# board_1_4_FixMosfetGND_v.net
KiCad netlist of a schematic drawn in EAGLE
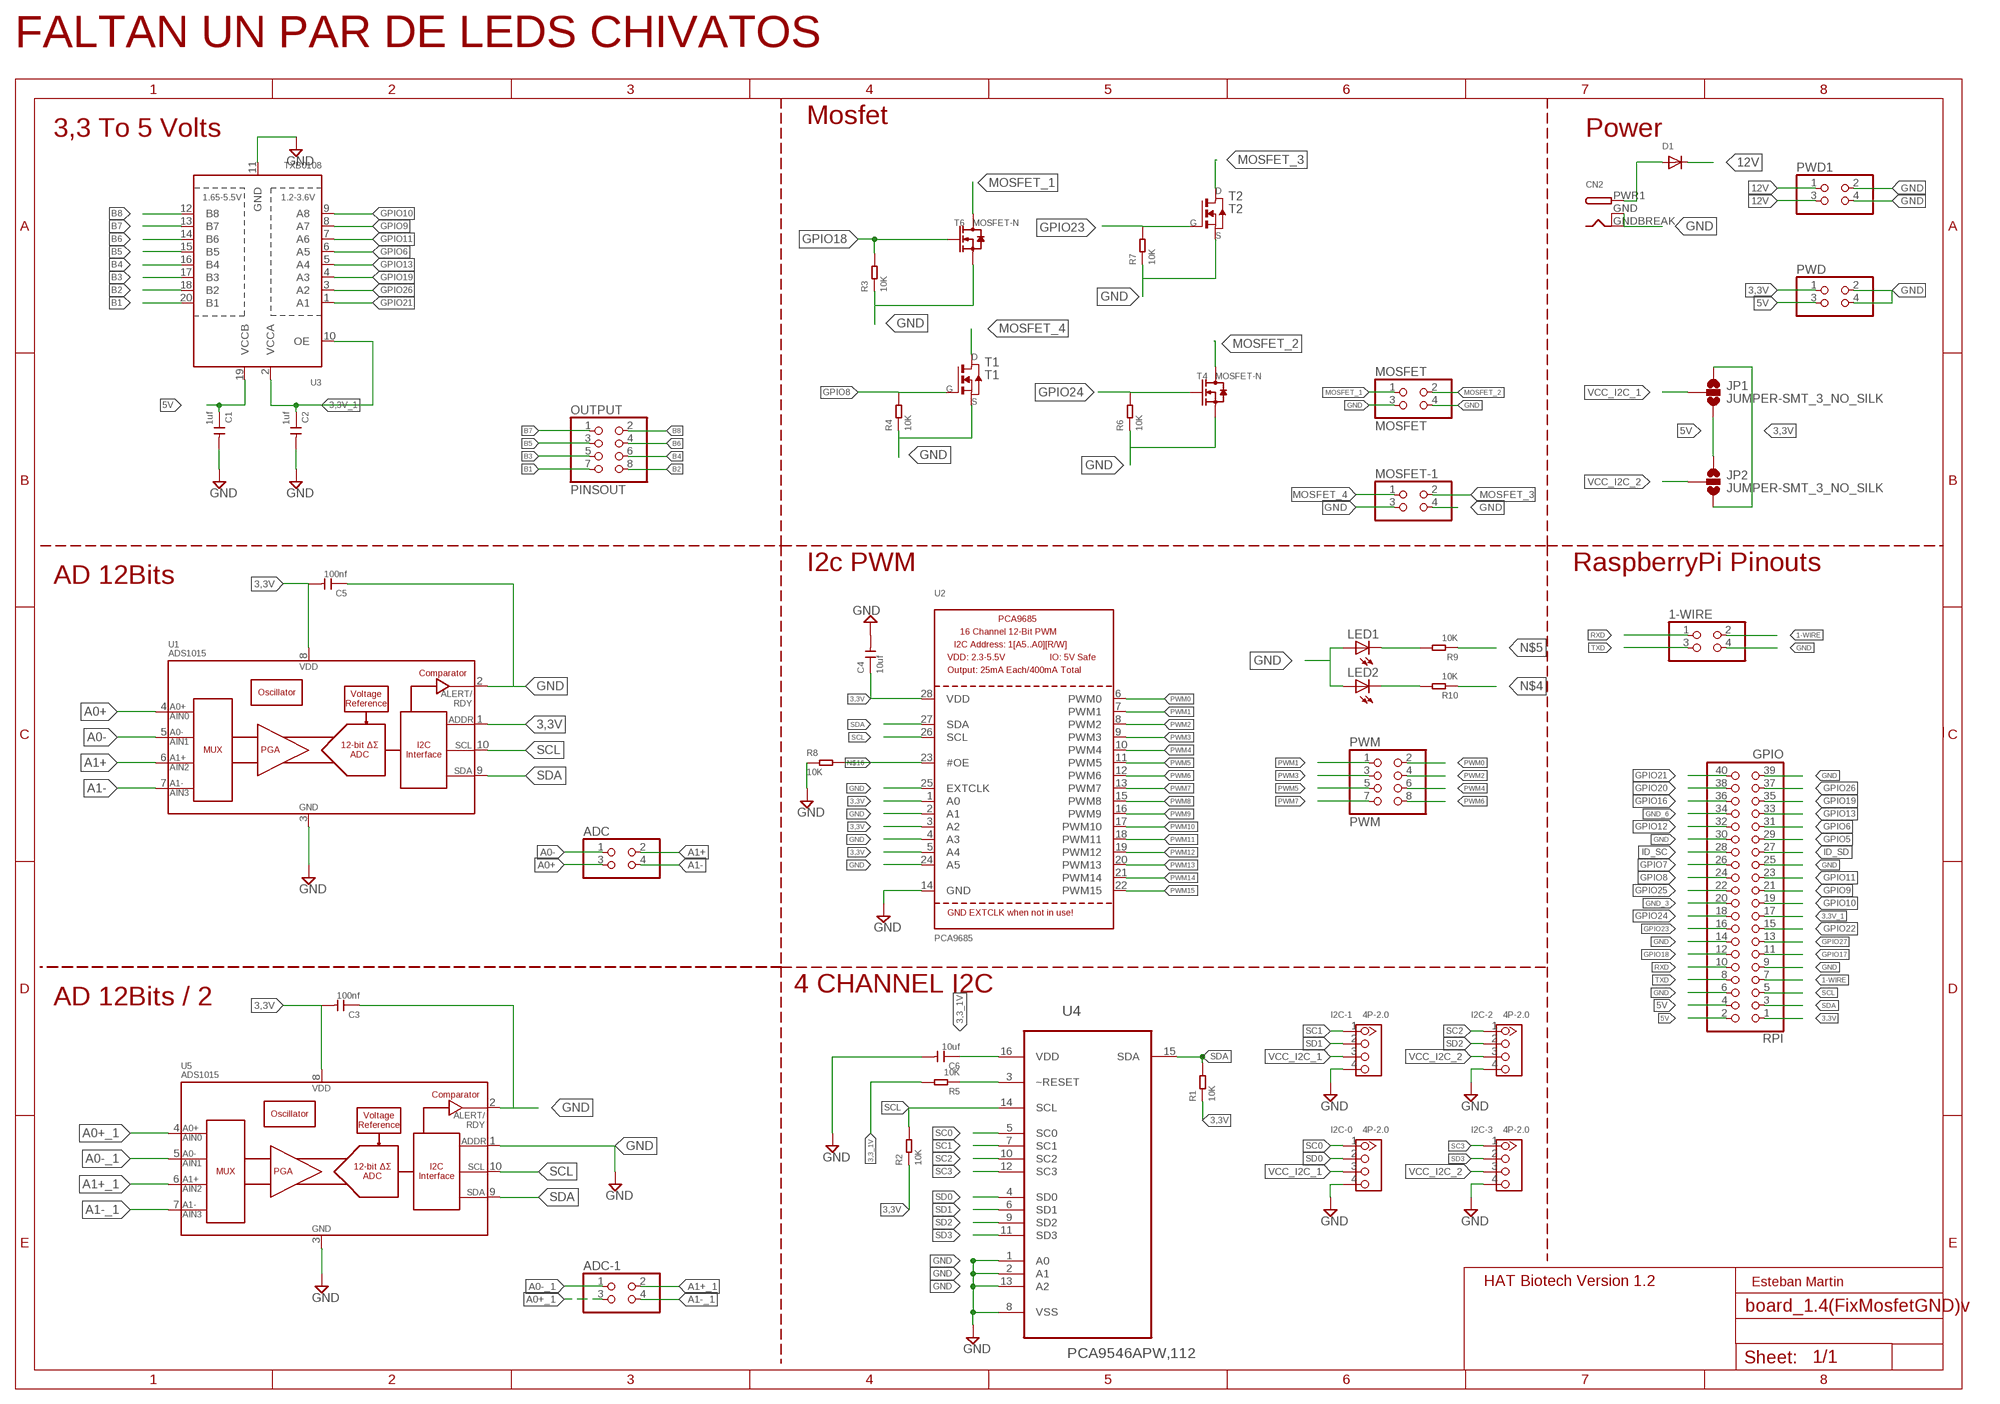
[diagram p0: schematic, sheet 1]

(export (version "E")
  (design (tool "Eeschema 10.0.6"))
  (components
    (comp (ref "1-WIRE")
      (value "PINHD-2X2")
      (footprint "eagle-import:2X02")
      (libsource (lib "eagle-import") (part "PINHD-2X2"))
    )
    (comp (ref "ADC")
      (value "PINHD-2X2")
      (footprint "eagle-import:2X02")
      (libsource (lib "eagle-import") (part "PINHD-2X2"))
    )
    (comp (ref "ADC-1")
      (value "PINHD-2X2")
      (footprint "eagle-import:2X02")
      (libsource (lib "eagle-import") (part "PINHD-2X2"))
    )
    (comp (ref "C1")
      (value "1uf")
      (footprint "eagle-import:C0805")
      (fields (field (name "MPN") "CC0805KKX7R8BB105"))
      (libsource (lib "eagle-import") (part "CERAMIC-1UF-25V-10%-X7R(0805)"))
    )
    (comp (ref "C2")
      (value "1uf")
      (footprint "eagle-import:C0805")
      (fields (field (name "MPN") "CC0805KKX7R8BB105"))
      (libsource (lib "eagle-import") (part "CERAMIC-1UF-25V-10%-X7R(0805)"))
    )
    (comp (ref "C3")
      (value "100nf")
      (footprint "eagle-import:C0805")
      (fields (field (name "MPN") "CC0805KRX7R9BB104"))
      (libsource (lib "eagle-import") (part "CERAMIC-100NF-50V-10%-X7R(0805)"))
    )
    (comp (ref "C4")
      (value "10uf")
      (footprint "eagle-import:C0805")
      (fields (field (name "MPN") "CC0805KKX7R8BB105"))
      (libsource (lib "eagle-import") (part "CERAMIC-1UF-25V-10%-X7R(0805)"))
    )
    (comp (ref "C5")
      (value "100nf")
      (footprint "eagle-import:C0805")
      (fields (field (name "MPN") "CC0805KRX7R9BB104"))
      (libsource (lib "eagle-import") (part "CERAMIC-100NF-50V-10%-X7R(0805)"))
    )
    (comp (ref "C6")
      (value "10uf")
      (footprint "eagle-import:C0805")
      (fields (field (name "MPN") "CC0805KKX7R8BB105"))
      (libsource (lib "eagle-import") (part "CERAMIC-1UF-25V-10%-X7R(0805)"))
    )
    (comp (ref "CN2")
      (value "DCBARRELSMT")
      (footprint "eagle-import:DCJACK_2MM_SMT")
      (libsource (lib "eagle-import") (part "DCBARRELSMT"))
    )
    (comp (ref "D1")
      (value "DIODESOD-123")
      (footprint "eagle-import:SOD-123")
      (libsource (lib "eagle-import") (part "DIODESOD-123"))
    )
    (comp (ref "I2C-0")
      (value "4P-2.0")
      (footprint "eagle-import:HW4-2.0")
      (libsource (lib "eagle-import") (part "GROVE-CONNECTOR-DIP(4P-2.0)"))
    )
    (comp (ref "I2C-1")
      (value "4P-2.0")
      (footprint "eagle-import:HW4-2.0")
      (libsource (lib "eagle-import") (part "GROVE-CONNECTOR-DIP(4P-2.0)"))
    )
    (comp (ref "I2C-2")
      (value "4P-2.0")
      (footprint "eagle-import:HW4-2.0")
      (libsource (lib "eagle-import") (part "GROVE-CONNECTOR-DIP(4P-2.0)"))
    )
    (comp (ref "I2C-3")
      (value "4P-2.0")
      (footprint "eagle-import:HW4-2.0")
      (libsource (lib "eagle-import") (part "GROVE-CONNECTOR-DIP(4P-2.0)"))
    )
    (comp (ref "JP1")
      (value "JUMPER-SMT_3_NO_SILK")
      (footprint "eagle-import:SMT-JUMPER_3_NO_SILK")
      (libsource (lib "eagle-import") (part "JUMPER-SMT_3_NO_SILK"))
    )
    (comp (ref "JP2")
      (value "JUMPER-SMT_3_NO_SILK")
      (footprint "eagle-import:SMT-JUMPER_3_NO_SILK")
      (libsource (lib "eagle-import") (part "JUMPER-SMT_3_NO_SILK"))
    )
    (comp (ref "LED1")
      (value "LED")
      (footprint "eagle-import:SMARTLED-TTW")
      (libsource (lib "eagle-import") (part "LED"))
    )
    (comp (ref "LED2")
      (value "LED")
      (footprint "eagle-import:SMARTLED-TTW")
      (libsource (lib "eagle-import") (part "LED"))
    )
    (comp (ref "MOSFET")
      (value "MOSFET")
      (footprint "eagle-import:2X02")
      (libsource (lib "eagle-import") (part "PINHD-2X2"))
    )
    (comp (ref "MOSFET-1")
      (value "PINHD-2X2")
      (footprint "eagle-import:2X02")
      (libsource (lib "eagle-import") (part "PINHD-2X2"))
    )
    (comp (ref "OUTPUT")
      (value "PINSOUT")
      (footprint "eagle-import:2X04")
      (libsource (lib "eagle-import") (part "PINHD-2X4"))
    )
    (comp (ref "PWD")
      (value "PINHD-2X2")
      (footprint "eagle-import:2X02")
      (libsource (lib "eagle-import") (part "PINHD-2X2"))
    )
    (comp (ref "PWD1")
      (value "PINHD-2X2")
      (footprint "eagle-import:2X02")
      (libsource (lib "eagle-import") (part "PINHD-2X2"))
    )
    (comp (ref "PWM")
      (value "PWM")
      (footprint "eagle-import:2X04")
      (libsource (lib "eagle-import") (part "PINHD-2X4"))
    )
    (comp (ref "R1")
      (value "10K")
      (footprint "eagle-import:R0805")
      (fields (field (name "MPN") "RC0805FR-0710KL"))
      (libsource (lib "eagle-import") (part "SMD-RES-10K-1%-1/8W(0805)"))
    )
    (comp (ref "R2")
      (value "10K")
      (footprint "eagle-import:R0805")
      (fields (field (name "MPN") "RC0805FR-0710KL"))
      (libsource (lib "eagle-import") (part "SMD-RES-10K-1%-1/8W(0805)"))
    )
    (comp (ref "R3")
      (value "10K")
      (footprint "eagle-import:R0805")
      (fields (field (name "MPN") "RC0805FR-0710KL"))
      (libsource (lib "eagle-import") (part "SMD-RES-10K-1%-1/8W(0805)"))
    )
    (comp (ref "R4")
      (value "10K")
      (footprint "eagle-import:R0805")
      (fields (field (name "MPN") "RC0805FR-0710KL"))
      (libsource (lib "eagle-import") (part "SMD-RES-10K-1%-1/8W(0805)"))
    )
    (comp (ref "R5")
      (value "10K")
      (footprint "eagle-import:R0805")
      (fields (field (name "MPN") "RC0805FR-0710KL"))
      (libsource (lib "eagle-import") (part "SMD-RES-10K-1%-1/8W(0805)"))
    )
    (comp (ref "R6")
      (value "10K")
      (footprint "eagle-import:R0805")
      (fields (field (name "MPN") "RC0805FR-0710KL"))
      (libsource (lib "eagle-import") (part "SMD-RES-10K-1%-1/8W(0805)"))
    )
    (comp (ref "R7")
      (value "10K")
      (footprint "eagle-import:R0805")
      (fields (field (name "MPN") "RC0805FR-0710KL"))
      (libsource (lib "eagle-import") (part "SMD-RES-10K-1%-1/8W(0805)"))
    )
    (comp (ref "R8")
      (value "10K")
      (footprint "eagle-import:R0805")
      (fields (field (name "MPN") "RC0805FR-0710KL"))
      (libsource (lib "eagle-import") (part "SMD-RES-10K-1%-1/8W(0805)"))
    )
    (comp (ref "R9")
      (value "10K")
      (footprint "eagle-import:R0805")
      (fields (field (name "MPN") "RC0805FR-0710KL"))
      (libsource (lib "eagle-import") (part "SMD-RES-10K-1%-1/8W(0805)"))
    )
    (comp (ref "R10")
      (value "10K")
      (footprint "eagle-import:R0805")
      (fields (field (name "MPN") "RC0805FR-0710KL"))
      (libsource (lib "eagle-import") (part "SMD-RES-10K-1%-1/8W(0805)"))
    )
    (comp (ref "RPI")
      (value "GPIO")
      (footprint "eagle-import:2X20")
      (libsource (lib "eagle-import") (part "PINHD-2X20"))
    )
    (comp (ref "T1")
      (value "T1")
      (footprint "eagle-import:TO252")
      (libsource (lib "eagle-import") (part "NMOSFETTO252"))
    )
    (comp (ref "T2")
      (value "T2")
      (footprint "eagle-import:TO252")
      (libsource (lib "eagle-import") (part "NMOSFETTO252"))
    )
    (comp (ref "T4")
      (value "MOSFET-N")
      (footprint "eagle-import:SOT-23")
      (libsource (lib "eagle-import") (part "MOSFET-N"))
    )
    (comp (ref "T6")
      (value "MOSFET-N")
      (footprint "eagle-import:SOT-23")
      (libsource (lib "eagle-import") (part "MOSFET-N"))
    )
    (comp (ref "U1")
      (value "ADS1015")
      (footprint "eagle-import:MSOP10")
      (libsource (lib "eagle-import") (part "ADS1015"))
    )
    (comp (ref "U2")
      (value "PCA9685")
      (footprint "eagle-import:TSSOP28")
      (libsource (lib "eagle-import") (part "PCA9685"))
    )
    (comp (ref "U3")
      (value "TXB0108")
      (footprint "eagle-import:TSSOP20")
      (libsource (lib "eagle-import") (part "TXB0108PWR"))
    )
    (comp (ref "U4")
      (value "PCA9546APW,112")
      (footprint "eagle-import:SOP65P640X110-16N")
      (libsource (lib "eagle-import") (part "PCA9546APW,112"))
    )
    (comp (ref "U5")
      (value "ADS1015")
      (footprint "eagle-import:MSOP10")
      (libsource (lib "eagle-import") (part "ADS1015"))
    )
  )
  (nets
    (net (code "1") (name "1-WIRE") (class "Default")
      (node (ref "1-WIRE") (pin "2") (pinfunction "2_2") (pintype "passive"))
      (node (ref "RPI") (pin "7") (pinfunction "7_7") (pintype "passive"))
    )
    (net (code "2") (name "3,3V") (class "Default")
      (node (ref "C3") (pin "2") (pinfunction "2_2") (pintype "passive"))
      (node (ref "C4") (pin "1") (pinfunction "1_1") (pintype "passive"))
      (node (ref "C5") (pin "2") (pinfunction "2_2") (pintype "passive"))
      (node (ref "JP1") (pin "1") (pinfunction "1_1") (pintype "passive"))
      (node (ref "JP2") (pin "3") (pinfunction "3_3") (pintype "passive"))
      (node (ref "PWD") (pin "1") (pinfunction "1_1") (pintype "passive"))
      (node (ref "R1") (pin "1") (pinfunction "1_1") (pintype "passive"))
      (node (ref "R2") (pin "1") (pinfunction "1_1") (pintype "passive"))
      (node (ref "RPI") (pin "1") (pinfunction "1_1") (pintype "passive"))
      (node (ref "U1") (pin "1") (pinfunction "ADDR_1") (pintype "bidirectional"))
      (node (ref "U1") (pin "8") (pinfunction "VDD_8") (pintype "bidirectional"))
      (node (ref "U2") (pin "1") (pinfunction "A0_1") (pintype "bidirectional"))
      (node (ref "U2") (pin "28") (pinfunction "VDD_28") (pintype "power_in"))
      (node (ref "U2") (pin "3") (pinfunction "A2_3") (pintype "bidirectional"))
      (node (ref "U2") (pin "5") (pinfunction "A4_5") (pintype "bidirectional"))
      (node (ref "U5") (pin "8") (pinfunction "VDD_8") (pintype "bidirectional"))
    )
    (net (code "3") (name "3,3V_1") (class "Default")
      (node (ref "C2") (pin "1") (pinfunction "1_1") (pintype "passive"))
      (node (ref "RPI") (pin "17") (pinfunction "17_17") (pintype "passive"))
      (node (ref "U3") (pin "10") (pinfunction "OE_10") (pintype "bidirectional"))
      (node (ref "U3") (pin "2") (pinfunction "VCCA_2") (pintype "bidirectional"))
    )
    (net (code "4") (name "3,3_1V") (class "Default")
      (node (ref "C6") (pin "1") (pinfunction "1_1") (pintype "passive"))
      (node (ref "R5") (pin "2") (pinfunction "2_2") (pintype "passive"))
      (node (ref "U4") (pin "16") (pinfunction "VDD_16") (pintype "power_in"))
    )
    (net (code "5") (name "5V") (class "Default")
      (node (ref "C1") (pin "1") (pinfunction "1_1") (pintype "passive"))
      (node (ref "JP1") (pin "3") (pinfunction "3_3") (pintype "passive"))
      (node (ref "JP2") (pin "1") (pinfunction "1_1") (pintype "passive"))
      (node (ref "PWD") (pin "3") (pinfunction "3_3") (pintype "passive"))
      (node (ref "RPI") (pin "2") (pinfunction "2_2") (pintype "passive"))
      (node (ref "RPI") (pin "4") (pinfunction "4_4") (pintype "passive"))
      (node (ref "U3") (pin "19") (pinfunction "VCCB_19") (pintype "bidirectional"))
    )
    (net (code "6") (name "12V") (class "Default")
      (node (ref "D1") (pin "C") (pinfunction "C_C") (pintype "passive"))
      (node (ref "PWD1") (pin "1") (pinfunction "1_1") (pintype "passive"))
      (node (ref "PWD1") (pin "3") (pinfunction "3_3") (pintype "passive"))
    )
    (net (code "7") (name "A0+") (class "Default")
      (node (ref "ADC") (pin "3") (pinfunction "3_3") (pintype "passive"))
      (node (ref "U1") (pin "4") (pinfunction "AIN0_4") (pintype "bidirectional"))
    )
    (net (code "8") (name "A0+_1") (class "Default")
      (node (ref "ADC-1") (pin "3") (pinfunction "3_3") (pintype "passive"))
      (node (ref "U5") (pin "4") (pinfunction "AIN0_4") (pintype "bidirectional"))
    )
    (net (code "9") (name "A0-") (class "Default")
      (node (ref "ADC") (pin "1") (pinfunction "1_1") (pintype "passive"))
      (node (ref "U1") (pin "5") (pinfunction "AIN1_5") (pintype "bidirectional"))
    )
    (net (code "10") (name "A0-_1") (class "Default")
      (node (ref "ADC-1") (pin "1") (pinfunction "1_1") (pintype "passive"))
      (node (ref "U5") (pin "5") (pinfunction "AIN1_5") (pintype "bidirectional"))
    )
    (net (code "11") (name "A1+") (class "Default")
      (node (ref "ADC") (pin "2") (pinfunction "2_2") (pintype "passive"))
      (node (ref "U1") (pin "6") (pinfunction "AIN2_6") (pintype "bidirectional"))
    )
    (net (code "12") (name "A1+_1") (class "Default")
      (node (ref "ADC-1") (pin "2") (pinfunction "2_2") (pintype "passive"))
      (node (ref "U5") (pin "6") (pinfunction "AIN2_6") (pintype "bidirectional"))
    )
    (net (code "13") (name "A1-") (class "Default")
      (node (ref "ADC") (pin "4") (pinfunction "4_4") (pintype "passive"))
      (node (ref "U1") (pin "7") (pinfunction "AIN3_7") (pintype "bidirectional"))
    )
    (net (code "14") (name "A1-_1") (class "Default")
      (node (ref "ADC-1") (pin "4") (pinfunction "4_4") (pintype "passive"))
      (node (ref "U5") (pin "7") (pinfunction "AIN3_7") (pintype "bidirectional"))
    )
    (net (code "15") (name "B1") (class "Default")
      (node (ref "OUTPUT") (pin "7") (pinfunction "7_7") (pintype "passive"))
      (node (ref "U3") (pin "20") (pinfunction "B1_20") (pintype "bidirectional"))
    )
    (net (code "16") (name "B2") (class "Default")
      (node (ref "OUTPUT") (pin "8") (pinfunction "8_8") (pintype "passive"))
      (node (ref "U3") (pin "18") (pinfunction "B2_18") (pintype "bidirectional"))
    )
    (net (code "17") (name "B3") (class "Default")
      (node (ref "OUTPUT") (pin "5") (pinfunction "5_5") (pintype "passive"))
      (node (ref "U3") (pin "17") (pinfunction "B3_17") (pintype "bidirectional"))
    )
    (net (code "18") (name "B4") (class "Default")
      (node (ref "OUTPUT") (pin "6") (pinfunction "6_6") (pintype "passive"))
      (node (ref "U3") (pin "16") (pinfunction "B4_16") (pintype "bidirectional"))
    )
    (net (code "19") (name "B5") (class "Default")
      (node (ref "OUTPUT") (pin "3") (pinfunction "3_3") (pintype "passive"))
      (node (ref "U3") (pin "15") (pinfunction "B5_15") (pintype "bidirectional"))
    )
    (net (code "20") (name "B6") (class "Default")
      (node (ref "OUTPUT") (pin "4") (pinfunction "4_4") (pintype "passive"))
      (node (ref "U3") (pin "14") (pinfunction "B6_14") (pintype "bidirectional"))
    )
    (net (code "21") (name "B7") (class "Default")
      (node (ref "OUTPUT") (pin "1") (pinfunction "1_1") (pintype "passive"))
      (node (ref "U3") (pin "13") (pinfunction "B7_13") (pintype "bidirectional"))
    )
    (net (code "22") (name "B8") (class "Default")
      (node (ref "OUTPUT") (pin "2") (pinfunction "2_2") (pintype "passive"))
      (node (ref "U3") (pin "12") (pinfunction "B8_12") (pintype "bidirectional"))
    )
    (net (code "23") (name "GND") (class "Default")
      (node (ref "1-WIRE") (pin "4") (pinfunction "4_4") (pintype "passive"))
      (node (ref "C1") (pin "2") (pinfunction "2_2") (pintype "passive"))
      (node (ref "C2") (pin "2") (pinfunction "2_2") (pintype "passive"))
      (node (ref "C3") (pin "1") (pinfunction "1_1") (pintype "passive"))
      (node (ref "C4") (pin "2") (pinfunction "2_2") (pintype "passive"))
      (node (ref "C5") (pin "1") (pinfunction "1_1") (pintype "passive"))
      (node (ref "C6") (pin "2") (pinfunction "2_2") (pintype "passive"))
      (node (ref "CN2") (pin "GND") (pinfunction "GNDBREAK_GND") (pintype "power_in"))
      (node (ref "CN2") (pin "GNDBREAK") (pinfunction "GND_GNDBREAK") (pintype "power_in"))
      (node (ref "I2C-0") (pin "4") (pinfunction "4_4") (pintype "bidirectional"))
      (node (ref "I2C-1") (pin "4") (pinfunction "4_4") (pintype "bidirectional"))
      (node (ref "I2C-2") (pin "4") (pinfunction "4_4") (pintype "bidirectional"))
      (node (ref "I2C-3") (pin "4") (pinfunction "4_4") (pintype "bidirectional"))
      (node (ref "LED1") (pin "A@1") (pinfunction "A_A@1") (pintype "passive"))
      (node (ref "LED2") (pin "A@1") (pinfunction "A_A@1") (pintype "passive"))
      (node (ref "MOSFET") (pin "3") (pinfunction "3_3") (pintype "passive"))
      (node (ref "MOSFET") (pin "4") (pinfunction "4_4") (pintype "passive"))
      (node (ref "MOSFET-1") (pin "3") (pinfunction "3_3") (pintype "passive"))
      (node (ref "MOSFET-1") (pin "4") (pinfunction "4_4") (pintype "passive"))
      (node (ref "PWD") (pin "2") (pinfunction "2_2") (pintype "passive"))
      (node (ref "PWD") (pin "4") (pinfunction "4_4") (pintype "passive"))
      (node (ref "PWD1") (pin "2") (pinfunction "2_2") (pintype "passive"))
      (node (ref "PWD1") (pin "4") (pinfunction "4_4") (pintype "passive"))
      (node (ref "R3") (pin "1") (pinfunction "1_1") (pintype "passive"))
      (node (ref "R4") (pin "1") (pinfunction "1_1") (pintype "passive"))
      (node (ref "R6") (pin "1") (pinfunction "1_1") (pintype "passive"))
      (node (ref "R7") (pin "1") (pinfunction "1_1") (pintype "passive"))
      (node (ref "R8") (pin "1") (pinfunction "1_1") (pintype "passive"))
      (node (ref "RPI") (pin "14") (pinfunction "14_14") (pintype "passive"))
      (node (ref "RPI") (pin "25") (pinfunction "25_25") (pintype "passive"))
      (node (ref "RPI") (pin "30") (pinfunction "30_30") (pintype "passive"))
      (node (ref "RPI") (pin "39") (pinfunction "39_39") (pintype "passive"))
      (node (ref "RPI") (pin "6") (pinfunction "6_6") (pintype "passive"))
      (node (ref "RPI") (pin "9") (pinfunction "9_9") (pintype "passive"))
      (node (ref "T1") (pin "2") (pinfunction "S_2") (pintype "passive"))
      (node (ref "T2") (pin "2") (pinfunction "S_2") (pintype "passive"))
      (node (ref "T4") (pin "2") (pinfunction "S_2") (pintype "passive"))
      (node (ref "T6") (pin "2") (pinfunction "S_2") (pintype "passive"))
      (node (ref "U1") (pin "2") (pinfunction "ALERT/RDY_2") (pintype "bidirectional"))
      (node (ref "U1") (pin "3") (pinfunction "VSS_3") (pintype "bidirectional"))
      (node (ref "U2") (pin "14") (pinfunction "GND_14") (pintype "power_in"))
      (node (ref "U2") (pin "2") (pinfunction "A1_2") (pintype "bidirectional"))
      (node (ref "U2") (pin "24") (pinfunction "A5_24") (pintype "bidirectional"))
      (node (ref "U2") (pin "25") (pinfunction "EXTCLK_25") (pintype "input"))
      (node (ref "U2") (pin "4") (pinfunction "A3_4") (pintype "bidirectional"))
      (node (ref "U3") (pin "11") (pinfunction "GND_11") (pintype "bidirectional"))
      (node (ref "U4") (pin "1") (pinfunction "A0_1") (pintype "input"))
      (node (ref "U4") (pin "13") (pinfunction "A2_13") (pintype "input"))
      (node (ref "U4") (pin "2") (pinfunction "A1_2") (pintype "input"))
      (node (ref "U4") (pin "8") (pinfunction "VSS_8") (pintype "passive"))
      (node (ref "U5") (pin "1") (pinfunction "ADDR_1") (pintype "bidirectional"))
      (node (ref "U5") (pin "2") (pinfunction "ALERT/RDY_2") (pintype "bidirectional"))
      (node (ref "U5") (pin "3") (pinfunction "VSS_3") (pintype "bidirectional"))
    )
    (net (code "24") (name "GND_3") (class "Default")
      (node (ref "RPI") (pin "20") (pinfunction "20_20") (pintype "passive"))
    )
    (net (code "25") (name "GND_6") (class "Default")
      (node (ref "RPI") (pin "34") (pinfunction "34_34") (pintype "passive"))
    )
    (net (code "26") (name "GPIO5") (class "Default")
      (node (ref "RPI") (pin "29") (pinfunction "29_29") (pintype "passive"))
    )
    (net (code "27") (name "GPIO6") (class "Default")
      (node (ref "RPI") (pin "31") (pinfunction "31_31") (pintype "passive"))
      (node (ref "U3") (pin "6") (pinfunction "A5_6") (pintype "bidirectional"))
    )
    (net (code "28") (name "GPIO7") (class "Default")
      (node (ref "RPI") (pin "26") (pinfunction "26_26") (pintype "passive"))
    )
    (net (code "29") (name "GPIO8") (class "Default")
      (node (ref "R4") (pin "2") (pinfunction "2_2") (pintype "passive"))
      (node (ref "RPI") (pin "24") (pinfunction "24_24") (pintype "passive"))
      (node (ref "T1") (pin "1") (pinfunction "G_1") (pintype "passive"))
    )
    (net (code "30") (name "GPIO9") (class "Default")
      (node (ref "RPI") (pin "21") (pinfunction "21_21") (pintype "passive"))
      (node (ref "U3") (pin "8") (pinfunction "A7_8") (pintype "bidirectional"))
    )
    (net (code "31") (name "GPIO10") (class "Default")
      (node (ref "RPI") (pin "19") (pinfunction "19_19") (pintype "passive"))
      (node (ref "U3") (pin "9") (pinfunction "A8_9") (pintype "bidirectional"))
    )
    (net (code "32") (name "GPIO11") (class "Default")
      (node (ref "RPI") (pin "23") (pinfunction "23_23") (pintype "passive"))
      (node (ref "U3") (pin "7") (pinfunction "A6_7") (pintype "bidirectional"))
    )
    (net (code "33") (name "GPIO12") (class "Default")
      (node (ref "RPI") (pin "32") (pinfunction "32_32") (pintype "passive"))
    )
    (net (code "34") (name "GPIO13") (class "Default")
      (node (ref "RPI") (pin "33") (pinfunction "33_33") (pintype "passive"))
      (node (ref "U3") (pin "5") (pinfunction "A4_5") (pintype "bidirectional"))
    )
    (net (code "35") (name "GPIO16") (class "Default")
      (node (ref "RPI") (pin "36") (pinfunction "36_36") (pintype "passive"))
    )
    (net (code "36") (name "GPIO17") (class "Default")
      (node (ref "RPI") (pin "11") (pinfunction "11_11") (pintype "passive"))
    )
    (net (code "37") (name "GPIO18") (class "Default")
      (node (ref "R3") (pin "2") (pinfunction "2_2") (pintype "passive"))
      (node (ref "RPI") (pin "12") (pinfunction "12_12") (pintype "passive"))
      (node (ref "T6") (pin "1") (pinfunction "G_1") (pintype "passive"))
    )
    (net (code "38") (name "GPIO19") (class "Default")
      (node (ref "RPI") (pin "35") (pinfunction "35_35") (pintype "passive"))
      (node (ref "U3") (pin "4") (pinfunction "A3_4") (pintype "bidirectional"))
    )
    (net (code "39") (name "GPIO20") (class "Default")
      (node (ref "RPI") (pin "38") (pinfunction "38_38") (pintype "passive"))
    )
    (net (code "40") (name "GPIO21") (class "Default")
      (node (ref "RPI") (pin "40") (pinfunction "40_40") (pintype "passive"))
      (node (ref "U3") (pin "1") (pinfunction "A1_1") (pintype "bidirectional"))
    )
    (net (code "41") (name "GPIO22") (class "Default")
      (node (ref "RPI") (pin "15") (pinfunction "15_15") (pintype "passive"))
    )
    (net (code "42") (name "GPIO23") (class "Default")
      (node (ref "R7") (pin "2") (pinfunction "2_2") (pintype "passive"))
      (node (ref "RPI") (pin "16") (pinfunction "16_16") (pintype "passive"))
      (node (ref "T2") (pin "1") (pinfunction "G_1") (pintype "passive"))
    )
    (net (code "43") (name "GPIO24") (class "Default")
      (node (ref "R6") (pin "2") (pinfunction "2_2") (pintype "passive"))
      (node (ref "RPI") (pin "18") (pinfunction "18_18") (pintype "passive"))
      (node (ref "T4") (pin "1") (pinfunction "G_1") (pintype "passive"))
    )
    (net (code "44") (name "GPIO25") (class "Default")
      (node (ref "RPI") (pin "22") (pinfunction "22_22") (pintype "passive"))
    )
    (net (code "45") (name "GPIO26") (class "Default")
      (node (ref "RPI") (pin "37") (pinfunction "37_37") (pintype "passive"))
      (node (ref "U3") (pin "3") (pinfunction "A2_3") (pintype "bidirectional"))
    )
    (net (code "46") (name "GPIO27") (class "Default")
      (node (ref "RPI") (pin "13") (pinfunction "13_13") (pintype "passive"))
    )
    (net (code "47") (name "ID_SC") (class "Default")
      (node (ref "RPI") (pin "28") (pinfunction "28_28") (pintype "passive"))
    )
    (net (code "48") (name "ID_SD") (class "Default")
      (node (ref "RPI") (pin "27") (pinfunction "27_27") (pintype "passive"))
    )
    (net (code "49") (name "MOSFET_1") (class "Default")
      (node (ref "MOSFET") (pin "1") (pinfunction "1_1") (pintype "passive"))
      (node (ref "T6") (pin "3") (pinfunction "D_3") (pintype "passive"))
    )
    (net (code "50") (name "MOSFET_2") (class "Default")
      (node (ref "MOSFET") (pin "2") (pinfunction "2_2") (pintype "passive"))
      (node (ref "T4") (pin "3") (pinfunction "D_3") (pintype "passive"))
    )
    (net (code "51") (name "MOSFET_3") (class "Default")
      (node (ref "MOSFET-1") (pin "2") (pinfunction "2_2") (pintype "passive"))
      (node (ref "T2") (pin "3") (pinfunction "D_3") (pintype "passive"))
    )
    (net (code "52") (name "MOSFET_4") (class "Default")
      (node (ref "MOSFET-1") (pin "1") (pinfunction "1_1") (pintype "passive"))
      (node (ref "T1") (pin "3") (pinfunction "D_3") (pintype "passive"))
    )
    (net (code "53") (name "N$4") (class "Default")
      (node (ref "R10") (pin "1") (pinfunction "1_1") (pintype "passive"))
    )
    (net (code "54") (name "N$5") (class "Default")
      (node (ref "R9") (pin "1") (pinfunction "1_1") (pintype "passive"))
    )
    (net (code "55") (name "N$16") (class "Default")
      (node (ref "R8") (pin "2") (pinfunction "2_2") (pintype "passive"))
      (node (ref "U2") (pin "23") (pinfunction "#OE_23") (pintype "input"))
    )
    (net (code "56") (name "Net-(CN2-PWR)") (class "Default")
      (node (ref "CN2") (pin "PWR1") (pinfunction "PWR_PWR1") (pintype "power_in"))
      (node (ref "D1") (pin "A") (pinfunction "A_A") (pintype "passive"))
    )
    (net (code "57") (name "Net-(LED1-C)") (class "Default")
      (node (ref "LED1") (pin "C@1") (pinfunction "C_C@1") (pintype "passive"))
      (node (ref "R9") (pin "2") (pinfunction "2_2") (pintype "passive"))
    )
    (net (code "58") (name "Net-(LED2-C)") (class "Default")
      (node (ref "LED2") (pin "C@1") (pinfunction "C_C@1") (pintype "passive"))
      (node (ref "R10") (pin "2") (pinfunction "2_2") (pintype "passive"))
    )
    (net (code "59") (name "Net-(U4-~{RESET})") (class "Default")
      (node (ref "R5") (pin "1") (pinfunction "1_1") (pintype "passive"))
      (node (ref "U4") (pin "3") (pinfunction "~{RESET}_3") (pintype "input"))
    )
    (net (code "60") (name "PWM0") (class "Default")
      (node (ref "PWM") (pin "2") (pinfunction "2_2") (pintype "passive"))
      (node (ref "U2") (pin "6") (pinfunction "PWM0_6") (pintype "output"))
    )
    (net (code "61") (name "PWM1") (class "Default")
      (node (ref "PWM") (pin "1") (pinfunction "1_1") (pintype "passive"))
      (node (ref "U2") (pin "7") (pinfunction "PWM1_7") (pintype "output"))
    )
    (net (code "62") (name "PWM2") (class "Default")
      (node (ref "PWM") (pin "4") (pinfunction "4_4") (pintype "passive"))
      (node (ref "U2") (pin "8") (pinfunction "PWM2_8") (pintype "output"))
    )
    (net (code "63") (name "PWM3") (class "Default")
      (node (ref "PWM") (pin "3") (pinfunction "3_3") (pintype "passive"))
      (node (ref "U2") (pin "9") (pinfunction "PWM3_9") (pintype "output"))
    )
    (net (code "64") (name "PWM4") (class "Default")
      (node (ref "PWM") (pin "6") (pinfunction "6_6") (pintype "passive"))
      (node (ref "U2") (pin "10") (pinfunction "PWM4_10") (pintype "output"))
    )
    (net (code "65") (name "PWM5") (class "Default")
      (node (ref "PWM") (pin "5") (pinfunction "5_5") (pintype "passive"))
      (node (ref "U2") (pin "11") (pinfunction "PWM5_11") (pintype "output"))
    )
    (net (code "66") (name "PWM6") (class "Default")
      (node (ref "PWM") (pin "8") (pinfunction "8_8") (pintype "passive"))
      (node (ref "U2") (pin "12") (pinfunction "PWM6_12") (pintype "output"))
    )
    (net (code "67") (name "PWM7") (class "Default")
      (node (ref "PWM") (pin "7") (pinfunction "7_7") (pintype "passive"))
      (node (ref "U2") (pin "13") (pinfunction "PWM7_13") (pintype "output"))
    )
    (net (code "68") (name "PWM8") (class "Default")
      (node (ref "U2") (pin "15") (pinfunction "PWM8_15") (pintype "output"))
    )
    (net (code "69") (name "PWM9") (class "Default")
      (node (ref "U2") (pin "16") (pinfunction "PWM9_16") (pintype "output"))
    )
    (net (code "70") (name "PWM10") (class "Default")
      (node (ref "U2") (pin "17") (pinfunction "PWM10_17") (pintype "output"))
    )
    (net (code "71") (name "PWM11") (class "Default")
      (node (ref "U2") (pin "18") (pinfunction "PWM11_18") (pintype "output"))
    )
    (net (code "72") (name "PWM12") (class "Default")
      (node (ref "U2") (pin "19") (pinfunction "PWM12_19") (pintype "output"))
    )
    (net (code "73") (name "PWM13") (class "Default")
      (node (ref "U2") (pin "20") (pinfunction "PWM13_20") (pintype "output"))
    )
    (net (code "74") (name "PWM14") (class "Default")
      (node (ref "U2") (pin "21") (pinfunction "PWM14_21") (pintype "output"))
    )
    (net (code "75") (name "PWM15") (class "Default")
      (node (ref "U2") (pin "22") (pinfunction "PWM15_22") (pintype "output"))
    )
    (net (code "76") (name "RXD") (class "Default")
      (node (ref "1-WIRE") (pin "1") (pinfunction "1_1") (pintype "passive"))
      (node (ref "RPI") (pin "10") (pinfunction "10_10") (pintype "passive"))
    )
    (net (code "77") (name "SC0") (class "Default")
      (node (ref "I2C-0") (pin "1") (pinfunction "1_1") (pintype "bidirectional"))
      (node (ref "U4") (pin "5") (pinfunction "SC0_5") (pintype "input"))
    )
    (net (code "78") (name "SC1") (class "Default")
      (node (ref "I2C-1") (pin "1") (pinfunction "1_1") (pintype "bidirectional"))
      (node (ref "U4") (pin "7") (pinfunction "SC1_7") (pintype "input"))
    )
    (net (code "79") (name "SC2") (class "Default")
      (node (ref "I2C-2") (pin "1") (pinfunction "1_1") (pintype "bidirectional"))
      (node (ref "U4") (pin "10") (pinfunction "SC2_10") (pintype "input"))
    )
    (net (code "80") (name "SC3") (class "Default")
      (node (ref "I2C-3") (pin "1") (pinfunction "1_1") (pintype "bidirectional"))
      (node (ref "U4") (pin "12") (pinfunction "SC3_12") (pintype "input"))
    )
    (net (code "81") (name "SCL") (class "Default")
      (node (ref "R2") (pin "2") (pinfunction "2_2") (pintype "passive"))
      (node (ref "RPI") (pin "5") (pinfunction "5_5") (pintype "passive"))
      (node (ref "U1") (pin "10") (pinfunction "SCL_10") (pintype "bidirectional"))
      (node (ref "U2") (pin "26") (pinfunction "SCL_26") (pintype "bidirectional"))
      (node (ref "U4") (pin "14") (pinfunction "SCL_14") (pintype "bidirectional"))
      (node (ref "U5") (pin "10") (pinfunction "SCL_10") (pintype "bidirectional"))
    )
    (net (code "82") (name "SD0") (class "Default")
      (node (ref "I2C-0") (pin "2") (pinfunction "2_2") (pintype "bidirectional"))
      (node (ref "U4") (pin "4") (pinfunction "SD0_4") (pintype "input"))
    )
    (net (code "83") (name "SD1") (class "Default")
      (node (ref "I2C-1") (pin "2") (pinfunction "2_2") (pintype "bidirectional"))
      (node (ref "U4") (pin "6") (pinfunction "SD1_6") (pintype "input"))
    )
    (net (code "84") (name "SD2") (class "Default")
      (node (ref "I2C-2") (pin "2") (pinfunction "2_2") (pintype "bidirectional"))
      (node (ref "U4") (pin "9") (pinfunction "SD2_9") (pintype "input"))
    )
    (net (code "85") (name "SD3") (class "Default")
      (node (ref "I2C-3") (pin "2") (pinfunction "2_2") (pintype "bidirectional"))
      (node (ref "U4") (pin "11") (pinfunction "SD3_11") (pintype "input"))
    )
    (net (code "86") (name "SDA") (class "Default")
      (node (ref "R1") (pin "2") (pinfunction "2_2") (pintype "passive"))
      (node (ref "RPI") (pin "3") (pinfunction "3_3") (pintype "passive"))
      (node (ref "U1") (pin "9") (pinfunction "SDA_9") (pintype "bidirectional"))
      (node (ref "U2") (pin "27") (pinfunction "SDA_27") (pintype "bidirectional"))
      (node (ref "U4") (pin "15") (pinfunction "SDA_15") (pintype "bidirectional"))
      (node (ref "U5") (pin "9") (pinfunction "SDA_9") (pintype "bidirectional"))
    )
    (net (code "87") (name "TXD") (class "Default")
      (node (ref "1-WIRE") (pin "3") (pinfunction "3_3") (pintype "passive"))
      (node (ref "RPI") (pin "8") (pinfunction "8_8") (pintype "passive"))
    )
    (net (code "88") (name "VCC_I2C_1") (class "Default")
      (node (ref "I2C-0") (pin "3") (pinfunction "3_3") (pintype "bidirectional"))
      (node (ref "I2C-1") (pin "3") (pinfunction "3_3") (pintype "bidirectional"))
      (node (ref "JP1") (pin "2") (pinfunction "2_2") (pintype "passive"))
    )
    (net (code "89") (name "VCC_I2C_2") (class "Default")
      (node (ref "I2C-2") (pin "3") (pinfunction "3_3") (pintype "bidirectional"))
      (node (ref "I2C-3") (pin "3") (pinfunction "3_3") (pintype "bidirectional"))
      (node (ref "JP2") (pin "2") (pinfunction "2_2") (pintype "passive"))
    )
  )
)
